# io.net
KiCad netlist of a schematic drawn in Altium Designer
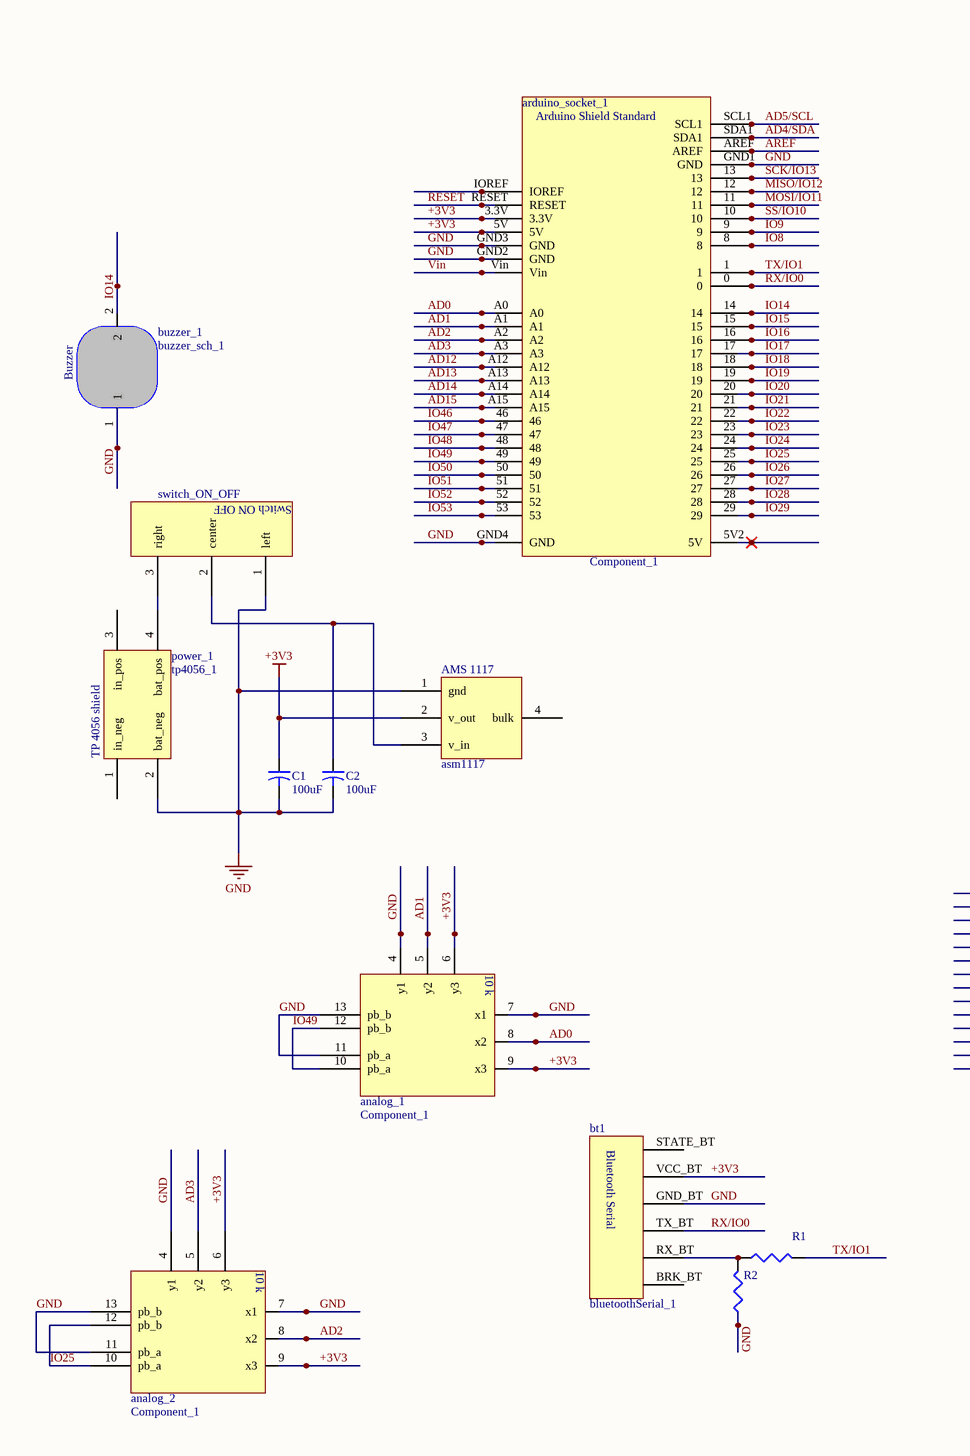
[diagram p0: io.SchDoc, left]
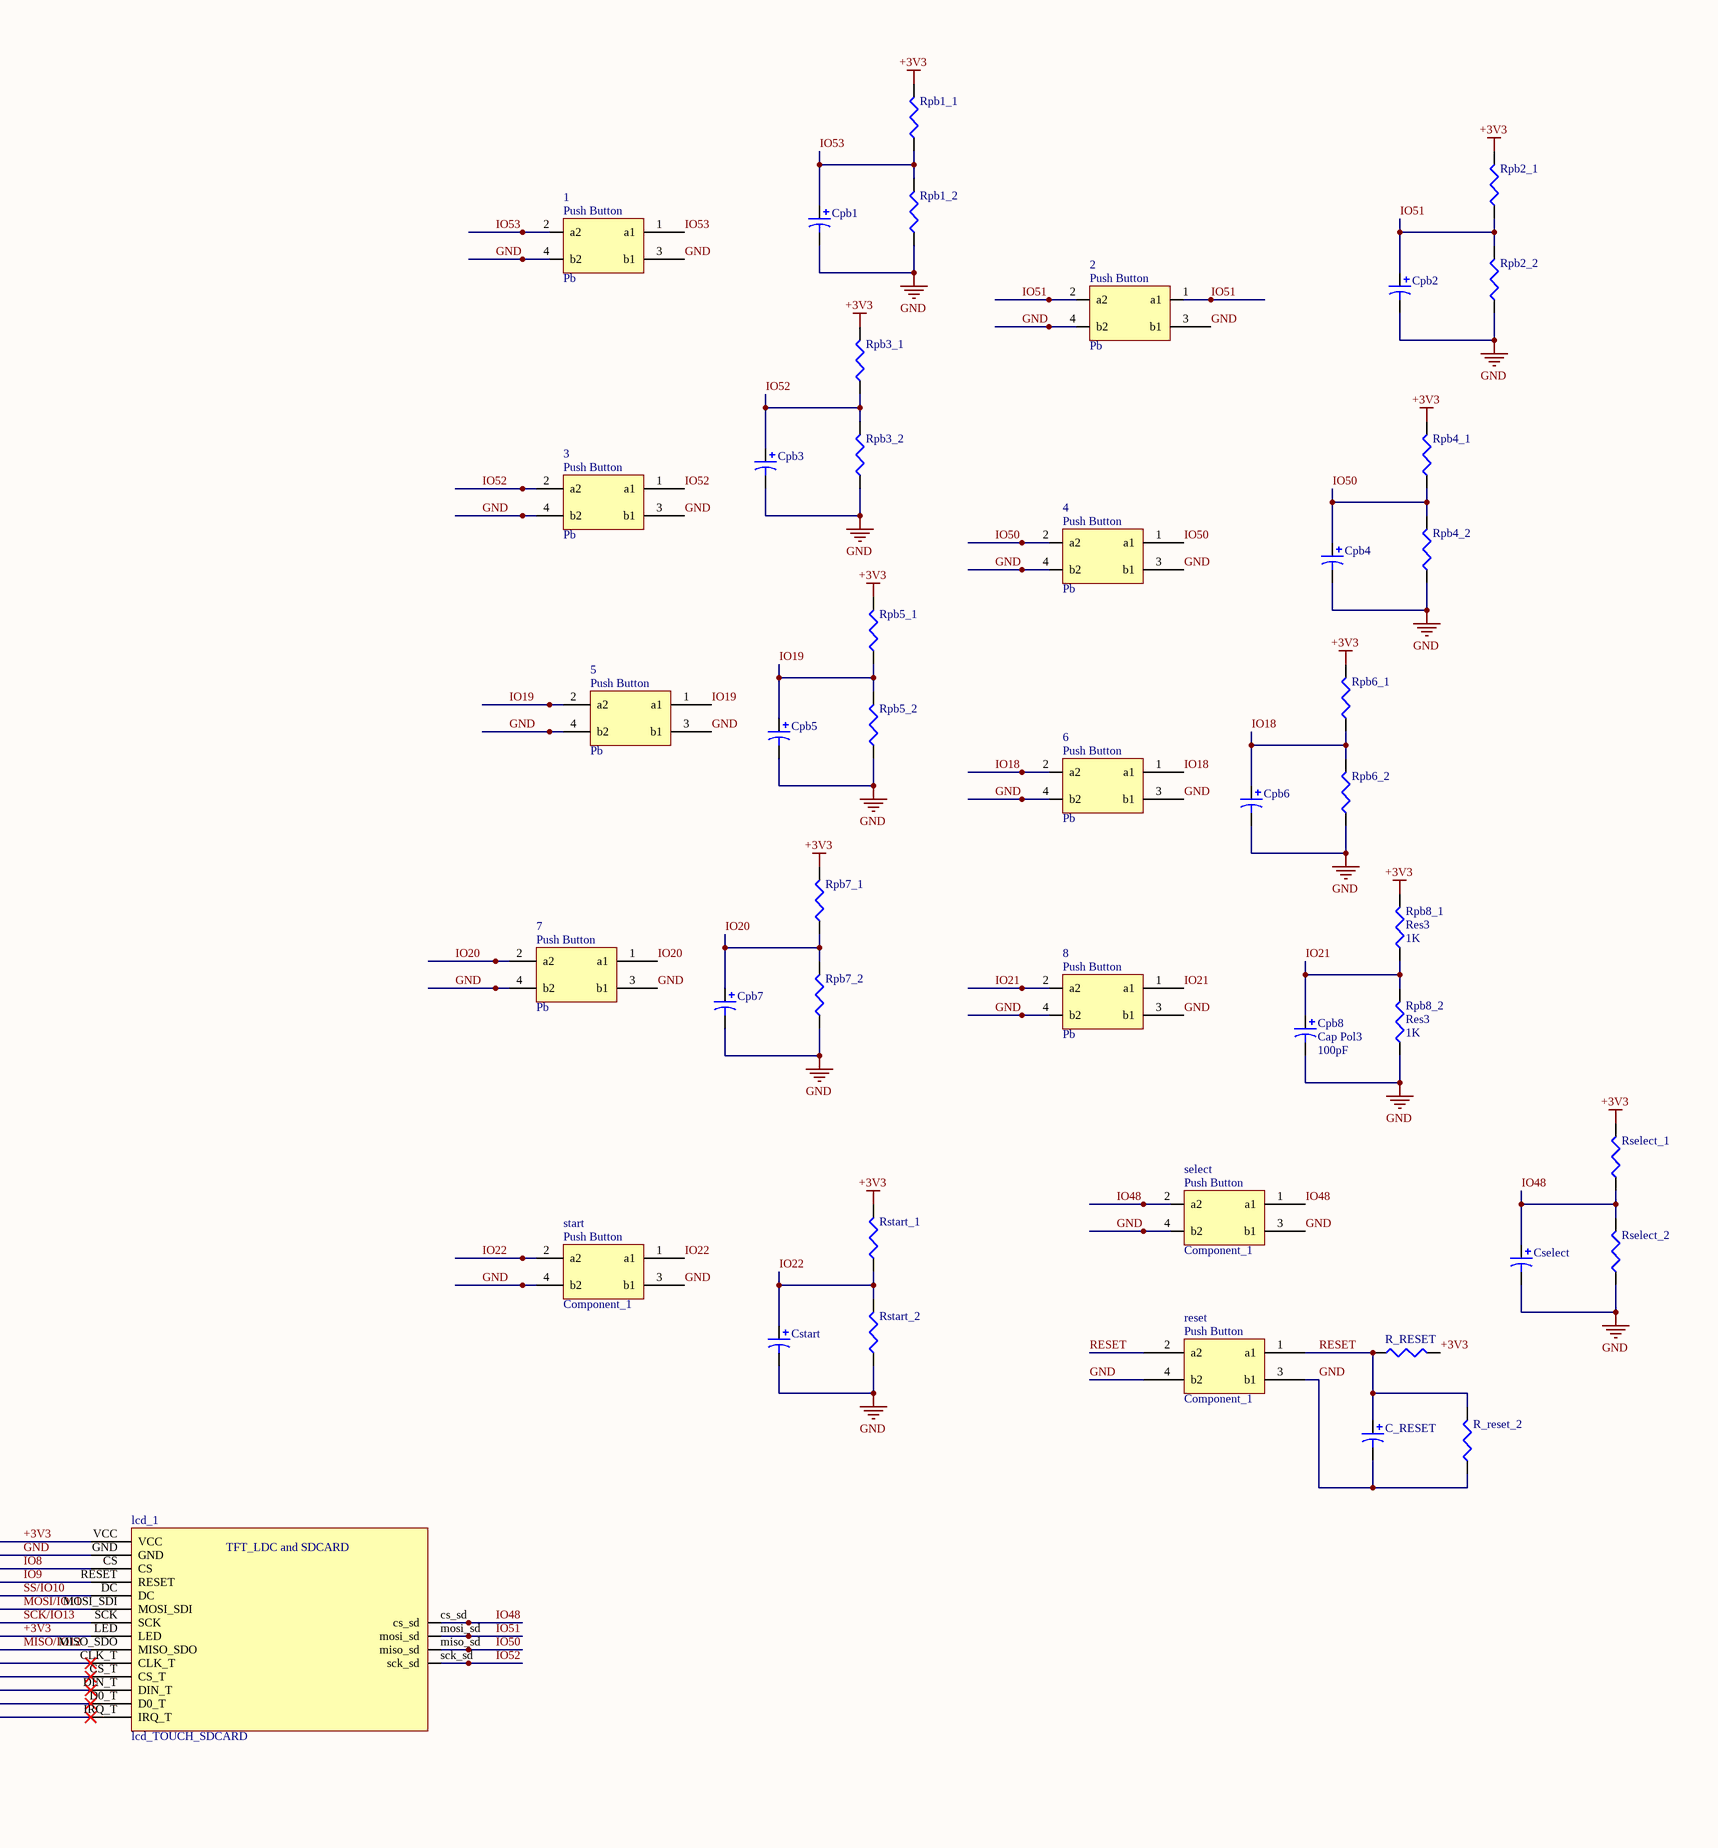
[diagram p1: io.SchDoc, right]

(export (version "E")
  (design (tool "Eeschema 10.0.6"))
  (components
    (comp (ref "1")
      (value "Pb")
      (footprint "PCBComponent_1")
      (libsource (lib "pushButton") (part "Component_1"))
    )
    (comp (ref "2")
      (value "Pb")
      (footprint "PCBComponent_1")
      (libsource (lib "pushButton") (part "Component_1"))
    )
    (comp (ref "3")
      (value "Pb")
      (footprint "PCBComponent_1")
      (libsource (lib "pushButton") (part "Component_1"))
    )
    (comp (ref "4")
      (value "Pb")
      (footprint "PCBComponent_1")
      (libsource (lib "pushButton") (part "Component_1"))
    )
    (comp (ref "5")
      (value "Pb")
      (footprint "PCBComponent_1")
      (libsource (lib "pushButton") (part "Component_1"))
    )
    (comp (ref "6")
      (value "Pb")
      (footprint "PCBComponent_1")
      (libsource (lib "pushButton") (part "Component_1"))
    )
    (comp (ref "7")
      (value "Pb")
      (footprint "PCBComponent_1")
      (libsource (lib "pushButton") (part "Component_1"))
    )
    (comp (ref "8")
      (value "Pb")
      (footprint "PCBComponent_1")
      (libsource (lib "pushButton") (part "Component_1"))
    )
    (comp (ref "analog_1")
      (value "Component_1")
      (footprint "PCBComponent_1")
      (libsource (lib "potDir_2eixos_v1_sch") (part "Component_1"))
    )
    (comp (ref "analog_2")
      (value "Component_1")
      (footprint "PCBComponent_1")
      (libsource (lib "potDir_2eixos_v1_sch") (part "Component_1"))
    )
    (comp (ref "arduino_socket_1")
      (value "Component_1")
      (footprint "arduino_due_cutPin")
      (libsource (lib "arduino_shield_stardard") (part "Component_1"))
    )
    (comp (ref "asm1117")
      (value "Component_1")
      (footprint "sot223_plasticPackage")
      (libsource (lib "AMS_1117_sch") (part "Component_1"))
    )
    (comp (ref "bt1")
      (value "bluetoothSerial_1")
      (footprint "bluetoothSerial_header")
      (libsource (lib "bluetooth_serial") (part "bluetoothSerial_1"))
    )
    (comp (ref "buzzer_1")
      (value "buzzer_sch_1")
      (footprint "buzzer_pcb_1")
      (libsource (lib "buzzer_sch") (part "buzzer_sch_1"))
    )
    (comp (ref "C1")
      (value "100uF")
      (footprint "capaEletrolitic_100uF_25v_smd")
      (description "Capacitor")
      (fields (field (name "Comment") "Cap2") (field (name "PUBLISHER") "Altium Limited"))
      (libsource (lib "Miscellaneous Devices") (part "Cap2"))
    )
    (comp (ref "C2")
      (value "100uF")
      (footprint "capaEletrolitic_100uF_25v_smd")
      (description "Capacitor")
      (fields (field (name "Comment") "Cap2") (field (name "PUBLISHER") "Altium Limited"))
      (libsource (lib "Miscellaneous Devices") (part "Cap2"))
    )
    (comp (ref "Cpb1")
      (value "Cap Pol3")
      (footprint "C0805")
      (description "Polarized Capacitor (Surface Mount)")
      (fields (field (name "PUBLISHER") "Altium Limited"))
      (libsource (lib "Miscellaneous Devices") (part "Cap Pol3"))
    )
    (comp (ref "Cpb2")
      (value "Cap Pol3")
      (footprint "C0805")
      (description "Polarized Capacitor (Surface Mount)")
      (fields (field (name "PUBLISHER") "Altium Limited"))
      (libsource (lib "Miscellaneous Devices") (part "Cap Pol3"))
    )
    (comp (ref "Cpb3")
      (value "Cap Pol3")
      (footprint "C0805")
      (description "Polarized Capacitor (Surface Mount)")
      (fields (field (name "PUBLISHER") "Altium Limited"))
      (libsource (lib "Miscellaneous Devices") (part "Cap Pol3"))
    )
    (comp (ref "Cpb4")
      (value "Cap Pol3")
      (footprint "C0805")
      (description "Polarized Capacitor (Surface Mount)")
      (fields (field (name "PUBLISHER") "Altium Limited"))
      (libsource (lib "Miscellaneous Devices") (part "Cap Pol3"))
    )
    (comp (ref "Cpb5")
      (value "Cap Pol3")
      (footprint "C0805")
      (description "Polarized Capacitor (Surface Mount)")
      (fields (field (name "PUBLISHER") "Altium Limited"))
      (libsource (lib "Miscellaneous Devices") (part "Cap Pol3"))
    )
    (comp (ref "Cpb6")
      (value "Cap Pol3")
      (footprint "C0805")
      (description "Polarized Capacitor (Surface Mount)")
      (fields (field (name "PUBLISHER") "Altium Limited"))
      (libsource (lib "Miscellaneous Devices") (part "Cap Pol3"))
    )
    (comp (ref "Cpb7")
      (value "Cap Pol3")
      (footprint "C0805")
      (description "Polarized Capacitor (Surface Mount)")
      (fields (field (name "PUBLISHER") "Altium Limited"))
      (libsource (lib "Miscellaneous Devices") (part "Cap Pol3"))
    )
    (comp (ref "Cpb8")
      (value "Cap Pol3")
      (footprint "C0805")
      (description "Polarized Capacitor (Surface Mount)")
      (fields (field (name "ALTIUM_VALUE") "100pF") (field (name "PUBLISHER") "Altium Limited"))
      (libsource (lib "Miscellaneous Devices") (part "Cap Pol3"))
    )
    (comp (ref "Cselect")
      (value "Cap Pol3")
      (footprint "C0805")
      (description "Polarized Capacitor (Surface Mount)")
      (fields (field (name "PUBLISHER") "Altium Limited"))
      (libsource (lib "Miscellaneous Devices") (part "Cap Pol3"))
    )
    (comp (ref "Cstart")
      (value "Cap Pol3")
      (footprint "C0805")
      (description "Polarized Capacitor (Surface Mount)")
      (fields (field (name "PUBLISHER") "Altium Limited"))
      (libsource (lib "Miscellaneous Devices") (part "Cap Pol3"))
    )
    (comp (ref "C_RESET")
      (value "Cap Pol3")
      (footprint "C0805")
      (description "Polarized Capacitor (Surface Mount)")
      (fields (field (name "PUBLISHER") "Altium Limited"))
      (libsource (lib "Miscellaneous Devices") (part "Cap Pol3"))
    )
    (comp (ref "lcd_1")
      (value "lcd_TOUCH_SDCARD")
      (footprint "PCB_LCDandTOUCH")
      (libsource (lib "lcd_TFT_and_TOUCH") (part "lcd_TOUCH_SDCARD"))
    )
    (comp (ref "power_1")
      (value "tp4056_1")
      (footprint "tp4056pcb_1")
      (libsource (lib "tp4056_shield_sch") (part "tp4056_1"))
    )
    (comp (ref "R1")
      (value "Res3")
      (footprint "J1-0603")
      (description "Resistor")
      (fields (field (name "PUBLISHER") "Altium Limited"))
      (libsource (lib "Miscellaneous Devices") (part "Res3"))
    )
    (comp (ref "R2")
      (value "Res3")
      (footprint "J1-0603")
      (description "Resistor")
      (fields (field (name "PUBLISHER") "Altium Limited"))
      (libsource (lib "Miscellaneous Devices") (part "Res3"))
    )
    (comp (ref "reset")
      (value "Component_1")
      (footprint "pb_6mm_1")
      (libsource (lib "pushButton") (part "Component_1"))
    )
    (comp (ref "Rpb1_1")
      (value "Res3")
      (footprint "J1-0603")
      (description "Resistor")
      (fields (field (name "PUBLISHER") "Altium Limited"))
      (libsource (lib "Miscellaneous Devices") (part "Res3"))
    )
    (comp (ref "Rpb1_2")
      (value "Res3")
      (footprint "J1-0603")
      (description "Resistor")
      (fields (field (name "PUBLISHER") "Altium Limited"))
      (libsource (lib "Miscellaneous Devices") (part "Res3"))
    )
    (comp (ref "Rpb2_1")
      (value "Res3")
      (footprint "J1-0603")
      (description "Resistor")
      (fields (field (name "PUBLISHER") "Altium Limited"))
      (libsource (lib "Miscellaneous Devices") (part "Res3"))
    )
    (comp (ref "Rpb2_2")
      (value "Res3")
      (footprint "J1-0603")
      (description "Resistor")
      (fields (field (name "PUBLISHER") "Altium Limited"))
      (libsource (lib "Miscellaneous Devices") (part "Res3"))
    )
    (comp (ref "Rpb3_1")
      (value "Res3")
      (footprint "J1-0603")
      (description "Resistor")
      (fields (field (name "PUBLISHER") "Altium Limited"))
      (libsource (lib "Miscellaneous Devices") (part "Res3"))
    )
    (comp (ref "Rpb3_2")
      (value "Res3")
      (footprint "J1-0603")
      (description "Resistor")
      (fields (field (name "PUBLISHER") "Altium Limited"))
      (libsource (lib "Miscellaneous Devices") (part "Res3"))
    )
    (comp (ref "Rpb4_1")
      (value "Res3")
      (footprint "J1-0603")
      (description "Resistor")
      (fields (field (name "PUBLISHER") "Altium Limited"))
      (libsource (lib "Miscellaneous Devices") (part "Res3"))
    )
    (comp (ref "Rpb4_2")
      (value "Res3")
      (footprint "J1-0603")
      (description "Resistor")
      (fields (field (name "PUBLISHER") "Altium Limited"))
      (libsource (lib "Miscellaneous Devices") (part "Res3"))
    )
    (comp (ref "Rpb5_1")
      (value "Res3")
      (footprint "J1-0603")
      (description "Resistor")
      (fields (field (name "PUBLISHER") "Altium Limited"))
      (libsource (lib "Miscellaneous Devices") (part "Res3"))
    )
    (comp (ref "Rpb5_2")
      (value "Res3")
      (footprint "J1-0603")
      (description "Resistor")
      (fields (field (name "PUBLISHER") "Altium Limited"))
      (libsource (lib "Miscellaneous Devices") (part "Res3"))
    )
    (comp (ref "Rpb6_1")
      (value "Res3")
      (footprint "J1-0603")
      (description "Resistor")
      (fields (field (name "PUBLISHER") "Altium Limited"))
      (libsource (lib "Miscellaneous Devices") (part "Res3"))
    )
    (comp (ref "Rpb6_2")
      (value "Res3")
      (footprint "J1-0603")
      (description "Resistor")
      (fields (field (name "PUBLISHER") "Altium Limited"))
      (libsource (lib "Miscellaneous Devices") (part "Res3"))
    )
    (comp (ref "Rpb7_1")
      (value "Res3")
      (footprint "J1-0603")
      (description "Resistor")
      (fields (field (name "PUBLISHER") "Altium Limited"))
      (libsource (lib "Miscellaneous Devices") (part "Res3"))
    )
    (comp (ref "Rpb7_2")
      (value "Res3")
      (footprint "J1-0603")
      (description "Resistor")
      (fields (field (name "PUBLISHER") "Altium Limited"))
      (libsource (lib "Miscellaneous Devices") (part "Res3"))
    )
    (comp (ref "Rpb8_1")
      (value "Res3")
      (footprint "J1-0603")
      (description "Resistor")
      (fields (field (name "ALTIUM_VALUE") "1K") (field (name "PUBLISHER") "Altium Limited"))
      (libsource (lib "Miscellaneous Devices") (part "Res3"))
    )
    (comp (ref "Rpb8_2")
      (value "Res3")
      (footprint "J1-0603")
      (description "Resistor")
      (fields (field (name "ALTIUM_VALUE") "1K") (field (name "PUBLISHER") "Altium Limited"))
      (libsource (lib "Miscellaneous Devices") (part "Res3"))
    )
    (comp (ref "Rselect_1")
      (value "Res3")
      (footprint "J1-0603")
      (description "Resistor")
      (fields (field (name "PUBLISHER") "Altium Limited"))
      (libsource (lib "Miscellaneous Devices") (part "Res3"))
    )
    (comp (ref "Rselect_2")
      (value "Res3")
      (footprint "J1-0603")
      (description "Resistor")
      (fields (field (name "PUBLISHER") "Altium Limited"))
      (libsource (lib "Miscellaneous Devices") (part "Res3"))
    )
    (comp (ref "Rstart_1")
      (value "Res3")
      (footprint "J1-0603")
      (description "Resistor")
      (fields (field (name "PUBLISHER") "Altium Limited"))
      (libsource (lib "Miscellaneous Devices") (part "Res3"))
    )
    (comp (ref "Rstart_2")
      (value "Res3")
      (footprint "J1-0603")
      (description "Resistor")
      (fields (field (name "PUBLISHER") "Altium Limited"))
      (libsource (lib "Miscellaneous Devices") (part "Res3"))
    )
    (comp (ref "R_RESET")
      (value "Res3")
      (footprint "J1-0603")
      (description "Resistor")
      (fields (field (name "PUBLISHER") "Altium Limited"))
      (libsource (lib "Miscellaneous Devices") (part "Res3"))
    )
    (comp (ref "R_reset_2")
      (value "Res3")
      (footprint "J1-0603")
      (description "Resistor")
      (fields (field (name "PUBLISHER") "Altium Limited"))
      (libsource (lib "Miscellaneous Devices") (part "Res3"))
    )
    (comp (ref "select")
      (value "Component_1")
      (footprint "PCBComponent_1")
      (libsource (lib "pushButton") (part "Component_1"))
    )
    (comp (ref "start")
      (value "Component_1")
      (footprint "PCBComponent_1")
      (libsource (lib "pushButton") (part "Component_1"))
    )
    (comp (ref "switch_ON_OFF")
      (value "switch_ON_OFF_1")
      (footprint "VERTICAL_SLIDE_SWITCH_SS12F23:PCBComponent_1")
      (libsource (lib "switch_ON_OFF") (part "switch_ON_OFF_1"))
    )
  )
  (nets
    (net (code "1") (name "+3V3") (class "Default")
      (node (ref "C1") (pin "1") (pinfunction "1_1") (pintype "passive"))
      (node (ref "R_RESET") (pin "2") (pinfunction "2_2") (pintype "passive"))
      (node (ref "Rpb1_1") (pin "2") (pinfunction "2_2") (pintype "passive"))
      (node (ref "Rpb2_1") (pin "2") (pinfunction "2_2") (pintype "passive"))
      (node (ref "Rpb3_1") (pin "2") (pinfunction "2_2") (pintype "passive"))
      (node (ref "Rpb4_1") (pin "2") (pinfunction "2_2") (pintype "passive"))
      (node (ref "Rpb5_1") (pin "2") (pinfunction "2_2") (pintype "passive"))
      (node (ref "Rpb6_1") (pin "2") (pinfunction "2_2") (pintype "passive"))
      (node (ref "Rpb7_1") (pin "2") (pinfunction "2_2") (pintype "passive"))
      (node (ref "Rpb8_1") (pin "2") (pinfunction "2_2") (pintype "passive"))
      (node (ref "Rselect_1") (pin "2") (pinfunction "2_2") (pintype "passive"))
      (node (ref "Rstart_1") (pin "2") (pinfunction "2_2") (pintype "passive"))
      (node (ref "analog_1") (pin "6") (pinfunction "y3_6") (pintype "passive"))
      (node (ref "analog_1") (pin "9") (pinfunction "x3_9") (pintype "passive"))
      (node (ref "analog_2") (pin "6") (pinfunction "y3_6") (pintype "passive"))
      (node (ref "analog_2") (pin "9") (pinfunction "x3_9") (pintype "passive"))
      (node (ref "arduino_socket_1") (pin "3.3V") (pinfunction "3.3V_3.3V") (pintype "passive"))
      (node (ref "arduino_socket_1") (pin "5V") (pinfunction "5V_5V") (pintype "passive"))
      (node (ref "asm1117") (pin "2") (pinfunction "v_out_2") (pintype "passive"))
      (node (ref "bt1") (pin "VCC_BT") (pinfunction "VCC_BT_VCC_BT") (pintype "passive"))
      (node (ref "lcd_1") (pin "LED") (pinfunction "LED_LED") (pintype "passive"))
      (node (ref "lcd_1") (pin "VCC") (pinfunction "VCC_VCC") (pintype "passive"))
    )
    (net (code "2") (name "/AD0") (class "Default")
      (node (ref "analog_1") (pin "8") (pinfunction "x2_8") (pintype "passive"))
      (node (ref "arduino_socket_1") (pin "A0") (pinfunction "A0_A0") (pintype "passive"))
    )
    (net (code "3") (name "/AD1") (class "Default")
      (node (ref "analog_1") (pin "5") (pinfunction "y2_5") (pintype "passive"))
      (node (ref "arduino_socket_1") (pin "A1") (pinfunction "A1_A1") (pintype "passive"))
    )
    (net (code "4") (name "/AD2") (class "Default")
      (node (ref "analog_2") (pin "8") (pinfunction "x2_8") (pintype "passive"))
      (node (ref "arduino_socket_1") (pin "A2") (pinfunction "A2_A2") (pintype "passive"))
    )
    (net (code "5") (name "/AD3") (class "Default")
      (node (ref "analog_2") (pin "5") (pinfunction "y2_5") (pintype "passive"))
      (node (ref "arduino_socket_1") (pin "A3") (pinfunction "A3_A3") (pintype "passive"))
    )
    (net (code "6") (name "/AD4{slash}SDA") (class "Default")
      (node (ref "arduino_socket_1") (pin "SDA1") (pinfunction "SDA1_SDA1") (pintype "passive"))
    )
    (net (code "7") (name "/AD5{slash}SCL") (class "Default")
      (node (ref "arduino_socket_1") (pin "SCL1") (pinfunction "SCL1_SCL1") (pintype "passive"))
    )
    (net (code "8") (name "/AD12") (class "Default")
      (node (ref "arduino_socket_1") (pin "A12") (pinfunction "A12_A12") (pintype "passive"))
    )
    (net (code "9") (name "/AD13") (class "Default")
      (node (ref "arduino_socket_1") (pin "A13") (pinfunction "A13_A13") (pintype "passive"))
    )
    (net (code "10") (name "/AD14") (class "Default")
      (node (ref "arduino_socket_1") (pin "A14") (pinfunction "A14_A14") (pintype "passive"))
    )
    (net (code "11") (name "/AD15") (class "Default")
      (node (ref "arduino_socket_1") (pin "A15") (pinfunction "A15_A15") (pintype "passive"))
    )
    (net (code "12") (name "/AREF") (class "Default")
      (node (ref "arduino_socket_1") (pin "AREF") (pinfunction "AREF_AREF") (pintype "passive"))
    )
    (net (code "13") (name "/IO8") (class "Default")
      (node (ref "arduino_socket_1") (pin "8") (pinfunction "8_8") (pintype "passive"))
      (node (ref "lcd_1") (pin "CS") (pinfunction "CS_CS") (pintype "passive"))
    )
    (net (code "14") (name "/IO9") (class "Default")
      (node (ref "arduino_socket_1") (pin "9") (pinfunction "9_9") (pintype "passive"))
      (node (ref "lcd_1") (pin "RESET") (pinfunction "RESET_RESET") (pintype "passive"))
    )
    (net (code "15") (name "/IO14") (class "Default")
      (node (ref "arduino_socket_1") (pin "14") (pinfunction "14_14") (pintype "passive"))
      (node (ref "buzzer_1") (pin "2") (pinfunction "2_2") (pintype "passive"))
    )
    (net (code "16") (name "/IO15") (class "Default")
      (node (ref "arduino_socket_1") (pin "15") (pinfunction "15_15") (pintype "passive"))
    )
    (net (code "17") (name "/IO16") (class "Default")
      (node (ref "arduino_socket_1") (pin "16") (pinfunction "16_16") (pintype "passive"))
    )
    (net (code "18") (name "/IO17") (class "Default")
      (node (ref "arduino_socket_1") (pin "17") (pinfunction "17_17") (pintype "passive"))
    )
    (net (code "19") (name "/IO18") (class "Default")
      (node (ref "6") (pin "1") (pinfunction "a1_1") (pintype "passive"))
      (node (ref "6") (pin "2") (pinfunction "a2_2") (pintype "passive"))
      (node (ref "Cpb6") (pin "1") (pinfunction "1_1") (pintype "passive"))
      (node (ref "Rpb6_1") (pin "1") (pinfunction "1_1") (pintype "passive"))
      (node (ref "Rpb6_2") (pin "2") (pinfunction "2_2") (pintype "passive"))
      (node (ref "arduino_socket_1") (pin "18") (pinfunction "18_18") (pintype "passive"))
    )
    (net (code "20") (name "/IO19") (class "Default")
      (node (ref "5") (pin "1") (pinfunction "a1_1") (pintype "passive"))
      (node (ref "5") (pin "2") (pinfunction "a2_2") (pintype "passive"))
      (node (ref "Cpb5") (pin "1") (pinfunction "1_1") (pintype "passive"))
      (node (ref "Rpb5_1") (pin "1") (pinfunction "1_1") (pintype "passive"))
      (node (ref "Rpb5_2") (pin "2") (pinfunction "2_2") (pintype "passive"))
      (node (ref "arduino_socket_1") (pin "19") (pinfunction "19_19") (pintype "passive"))
    )
    (net (code "21") (name "/IO20") (class "Default")
      (node (ref "7") (pin "1") (pinfunction "a1_1") (pintype "passive"))
      (node (ref "7") (pin "2") (pinfunction "a2_2") (pintype "passive"))
      (node (ref "Cpb7") (pin "1") (pinfunction "1_1") (pintype "passive"))
      (node (ref "Rpb7_1") (pin "1") (pinfunction "1_1") (pintype "passive"))
      (node (ref "Rpb7_2") (pin "2") (pinfunction "2_2") (pintype "passive"))
      (node (ref "arduino_socket_1") (pin "20") (pinfunction "20_20") (pintype "passive"))
    )
    (net (code "22") (name "/IO21") (class "Default")
      (node (ref "8") (pin "1") (pinfunction "a1_1") (pintype "passive"))
      (node (ref "8") (pin "2") (pinfunction "a2_2") (pintype "passive"))
      (node (ref "Cpb8") (pin "1") (pinfunction "1_1") (pintype "passive"))
      (node (ref "Rpb8_1") (pin "1") (pinfunction "1_1") (pintype "passive"))
      (node (ref "Rpb8_2") (pin "2") (pinfunction "2_2") (pintype "passive"))
      (node (ref "arduino_socket_1") (pin "21") (pinfunction "21_21") (pintype "passive"))
    )
    (net (code "23") (name "/IO22") (class "Default")
      (node (ref "Cstart") (pin "1") (pinfunction "1_1") (pintype "passive"))
      (node (ref "Rstart_1") (pin "1") (pinfunction "1_1") (pintype "passive"))
      (node (ref "Rstart_2") (pin "2") (pinfunction "2_2") (pintype "passive"))
      (node (ref "arduino_socket_1") (pin "22") (pinfunction "22_22") (pintype "passive"))
      (node (ref "start") (pin "1") (pinfunction "a1_1") (pintype "passive"))
      (node (ref "start") (pin "2") (pinfunction "a2_2") (pintype "passive"))
    )
    (net (code "24") (name "/IO23") (class "Default")
      (node (ref "arduino_socket_1") (pin "23") (pinfunction "23_23") (pintype "passive"))
    )
    (net (code "25") (name "/IO24") (class "Default")
      (node (ref "arduino_socket_1") (pin "24") (pinfunction "24_24") (pintype "passive"))
    )
    (net (code "26") (name "/IO25") (class "Default")
      (node (ref "analog_2") (pin "10") (pinfunction "pb_a_10") (pintype "passive"))
      (node (ref "analog_2") (pin "12") (pinfunction "pb_b_12") (pintype "passive"))
      (node (ref "arduino_socket_1") (pin "25") (pinfunction "25_25") (pintype "passive"))
    )
    (net (code "27") (name "/IO26") (class "Default")
      (node (ref "arduino_socket_1") (pin "26") (pinfunction "26_26") (pintype "passive"))
    )
    (net (code "28") (name "/IO27") (class "Default")
      (node (ref "arduino_socket_1") (pin "27") (pinfunction "27_27") (pintype "passive"))
    )
    (net (code "29") (name "/IO28") (class "Default")
      (node (ref "arduino_socket_1") (pin "28") (pinfunction "28_28") (pintype "passive"))
    )
    (net (code "30") (name "/IO29") (class "Default")
      (node (ref "arduino_socket_1") (pin "29") (pinfunction "29_29") (pintype "passive"))
    )
    (net (code "31") (name "/IO46") (class "Default")
      (node (ref "arduino_socket_1") (pin "46") (pinfunction "46_46") (pintype "passive"))
    )
    (net (code "32") (name "/IO47") (class "Default")
      (node (ref "arduino_socket_1") (pin "47") (pinfunction "47_47") (pintype "passive"))
    )
    (net (code "33") (name "/IO48") (class "Default")
      (node (ref "Cselect") (pin "1") (pinfunction "1_1") (pintype "passive"))
      (node (ref "Rselect_1") (pin "1") (pinfunction "1_1") (pintype "passive"))
      (node (ref "Rselect_2") (pin "2") (pinfunction "2_2") (pintype "passive"))
      (node (ref "arduino_socket_1") (pin "48") (pinfunction "48_48") (pintype "passive"))
      (node (ref "lcd_1") (pin "cs_sd") (pinfunction "cs_sd_cs_sd") (pintype "passive"))
      (node (ref "select") (pin "1") (pinfunction "a1_1") (pintype "passive"))
      (node (ref "select") (pin "2") (pinfunction "a2_2") (pintype "passive"))
    )
    (net (code "34") (name "/IO49") (class "Default")
      (node (ref "analog_1") (pin "10") (pinfunction "pb_a_10") (pintype "passive"))
      (node (ref "analog_1") (pin "12") (pinfunction "pb_b_12") (pintype "passive"))
      (node (ref "arduino_socket_1") (pin "49") (pinfunction "49_49") (pintype "passive"))
    )
    (net (code "35") (name "/IO50") (class "Default")
      (node (ref "4") (pin "1") (pinfunction "a1_1") (pintype "passive"))
      (node (ref "4") (pin "2") (pinfunction "a2_2") (pintype "passive"))
      (node (ref "Cpb4") (pin "1") (pinfunction "1_1") (pintype "passive"))
      (node (ref "Rpb4_1") (pin "1") (pinfunction "1_1") (pintype "passive"))
      (node (ref "Rpb4_2") (pin "2") (pinfunction "2_2") (pintype "passive"))
      (node (ref "arduino_socket_1") (pin "50") (pinfunction "50_50") (pintype "passive"))
      (node (ref "lcd_1") (pin "miso_sd") (pinfunction "miso_sd_miso_sd") (pintype "passive"))
    )
    (net (code "36") (name "/IO51") (class "Default")
      (node (ref "2") (pin "1") (pinfunction "a1_1") (pintype "passive"))
      (node (ref "2") (pin "2") (pinfunction "a2_2") (pintype "passive"))
      (node (ref "Cpb2") (pin "1") (pinfunction "1_1") (pintype "passive"))
      (node (ref "Rpb2_1") (pin "1") (pinfunction "1_1") (pintype "passive"))
      (node (ref "Rpb2_2") (pin "2") (pinfunction "2_2") (pintype "passive"))
      (node (ref "arduino_socket_1") (pin "51") (pinfunction "51_51") (pintype "passive"))
      (node (ref "lcd_1") (pin "mosi_sd") (pinfunction "mosi_sd_mosi_sd") (pintype "passive"))
    )
    (net (code "37") (name "/IO52") (class "Default")
      (node (ref "3") (pin "1") (pinfunction "a1_1") (pintype "passive"))
      (node (ref "3") (pin "2") (pinfunction "a2_2") (pintype "passive"))
      (node (ref "Cpb3") (pin "1") (pinfunction "1_1") (pintype "passive"))
      (node (ref "Rpb3_1") (pin "1") (pinfunction "1_1") (pintype "passive"))
      (node (ref "Rpb3_2") (pin "2") (pinfunction "2_2") (pintype "passive"))
      (node (ref "arduino_socket_1") (pin "52") (pinfunction "52_52") (pintype "passive"))
      (node (ref "lcd_1") (pin "sck_sd") (pinfunction "sck_sd_sck_sd") (pintype "passive"))
    )
    (net (code "38") (name "/IO53") (class "Default")
      (node (ref "1") (pin "1") (pinfunction "a1_1") (pintype "passive"))
      (node (ref "1") (pin "2") (pinfunction "a2_2") (pintype "passive"))
      (node (ref "Cpb1") (pin "1") (pinfunction "1_1") (pintype "passive"))
      (node (ref "Rpb1_1") (pin "1") (pinfunction "1_1") (pintype "passive"))
      (node (ref "Rpb1_2") (pin "2") (pinfunction "2_2") (pintype "passive"))
      (node (ref "arduino_socket_1") (pin "53") (pinfunction "53_53") (pintype "passive"))
    )
    (net (code "39") (name "/MISO{slash}IO12") (class "Default")
      (node (ref "arduino_socket_1") (pin "12") (pinfunction "12_12") (pintype "passive"))
      (node (ref "lcd_1") (pin "MISO_SDO") (pinfunction "MISO_SDO_MISO_SDO") (pintype "passive"))
    )
    (net (code "40") (name "/MOSI{slash}IO11") (class "Default")
      (node (ref "arduino_socket_1") (pin "11") (pinfunction "11_11") (pintype "passive"))
      (node (ref "lcd_1") (pin "MOSI_SDI") (pinfunction "MOSI_SDI_MOSI_SDI") (pintype "passive"))
    )
    (net (code "41") (name "/RESET") (class "Default")
      (node (ref "C_RESET") (pin "1") (pinfunction "1_1") (pintype "passive"))
      (node (ref "R_RESET") (pin "1") (pinfunction "1_1") (pintype "passive"))
      (node (ref "R_reset_2") (pin "2") (pinfunction "2_2") (pintype "passive"))
      (node (ref "arduino_socket_1") (pin "RESET") (pinfunction "RESET_RESET") (pintype "passive"))
      (node (ref "reset") (pin "1") (pinfunction "a1_1") (pintype "passive"))
      (node (ref "reset") (pin "2") (pinfunction "a2_2") (pintype "passive"))
    )
    (net (code "42") (name "/RX{slash}IO0") (class "Default")
      (node (ref "arduino_socket_1") (pin "0") (pinfunction "0_0") (pintype "passive"))
      (node (ref "bt1") (pin "TX_BT") (pinfunction "TX_BT_TX_BT") (pintype "passive"))
    )
    (net (code "43") (name "/SCK{slash}IO13") (class "Default")
      (node (ref "arduino_socket_1") (pin "13") (pinfunction "13_13") (pintype "passive"))
      (node (ref "lcd_1") (pin "SCK") (pinfunction "SCK_SCK") (pintype "passive"))
    )
    (net (code "44") (name "/SS{slash}IO10") (class "Default")
      (node (ref "arduino_socket_1") (pin "10") (pinfunction "10_10") (pintype "passive"))
      (node (ref "lcd_1") (pin "DC") (pinfunction "DC_DC") (pintype "passive"))
    )
    (net (code "45") (name "/TX{slash}IO1") (class "Default")
      (node (ref "R1") (pin "2") (pinfunction "2_2") (pintype "passive"))
      (node (ref "arduino_socket_1") (pin "1") (pinfunction "1_1") (pintype "passive"))
    )
    (net (code "46") (name "/Vin") (class "Default")
      (node (ref "arduino_socket_1") (pin "Vin") (pinfunction "Vin_Vin") (pintype "passive"))
    )
    (net (code "47") (name "GND") (class "Default")
      (node (ref "1") (pin "3") (pinfunction "b1_3") (pintype "passive"))
      (node (ref "1") (pin "4") (pinfunction "b2_4") (pintype "passive"))
      (node (ref "2") (pin "3") (pinfunction "b1_3") (pintype "passive"))
      (node (ref "2") (pin "4") (pinfunction "b2_4") (pintype "passive"))
      (node (ref "3") (pin "3") (pinfunction "b1_3") (pintype "passive"))
      (node (ref "3") (pin "4") (pinfunction "b2_4") (pintype "passive"))
      (node (ref "4") (pin "3") (pinfunction "b1_3") (pintype "passive"))
      (node (ref "4") (pin "4") (pinfunction "b2_4") (pintype "passive"))
      (node (ref "5") (pin "3") (pinfunction "b1_3") (pintype "passive"))
      (node (ref "5") (pin "4") (pinfunction "b2_4") (pintype "passive"))
      (node (ref "6") (pin "3") (pinfunction "b1_3") (pintype "passive"))
      (node (ref "6") (pin "4") (pinfunction "b2_4") (pintype "passive"))
      (node (ref "7") (pin "3") (pinfunction "b1_3") (pintype "passive"))
      (node (ref "7") (pin "4") (pinfunction "b2_4") (pintype "passive"))
      (node (ref "8") (pin "3") (pinfunction "b1_3") (pintype "passive"))
      (node (ref "8") (pin "4") (pinfunction "b2_4") (pintype "passive"))
      (node (ref "C1") (pin "2") (pinfunction "2_2") (pintype "passive"))
      (node (ref "C2") (pin "2") (pinfunction "2_2") (pintype "passive"))
      (node (ref "C_RESET") (pin "2") (pinfunction "2_2") (pintype "passive"))
      (node (ref "Cpb1") (pin "2") (pinfunction "2_2") (pintype "passive"))
      (node (ref "Cpb2") (pin "2") (pinfunction "2_2") (pintype "passive"))
      (node (ref "Cpb3") (pin "2") (pinfunction "2_2") (pintype "passive"))
      (node (ref "Cpb4") (pin "2") (pinfunction "2_2") (pintype "passive"))
      (node (ref "Cpb5") (pin "2") (pinfunction "2_2") (pintype "passive"))
      (node (ref "Cpb6") (pin "2") (pinfunction "2_2") (pintype "passive"))
      (node (ref "Cpb7") (pin "2") (pinfunction "2_2") (pintype "passive"))
      (node (ref "Cpb8") (pin "2") (pinfunction "2_2") (pintype "passive"))
      (node (ref "Cselect") (pin "2") (pinfunction "2_2") (pintype "passive"))
      (node (ref "Cstart") (pin "2") (pinfunction "2_2") (pintype "passive"))
      (node (ref "R2") (pin "1") (pinfunction "1_1") (pintype "passive"))
      (node (ref "R_reset_2") (pin "1") (pinfunction "1_1") (pintype "passive"))
      (node (ref "Rpb1_2") (pin "1") (pinfunction "1_1") (pintype "passive"))
      (node (ref "Rpb2_2") (pin "1") (pinfunction "1_1") (pintype "passive"))
      (node (ref "Rpb3_2") (pin "1") (pinfunction "1_1") (pintype "passive"))
      (node (ref "Rpb4_2") (pin "1") (pinfunction "1_1") (pintype "passive"))
      (node (ref "Rpb5_2") (pin "1") (pinfunction "1_1") (pintype "passive"))
      (node (ref "Rpb6_2") (pin "1") (pinfunction "1_1") (pintype "passive"))
      (node (ref "Rpb7_2") (pin "1") (pinfunction "1_1") (pintype "passive"))
      (node (ref "Rpb8_2") (pin "1") (pinfunction "1_1") (pintype "passive"))
      (node (ref "Rselect_2") (pin "1") (pinfunction "1_1") (pintype "passive"))
      (node (ref "Rstart_2") (pin "1") (pinfunction "1_1") (pintype "passive"))
      (node (ref "analog_1") (pin "11") (pinfunction "pb_a_11") (pintype "passive"))
      (node (ref "analog_1") (pin "13") (pinfunction "pb_b_13") (pintype "passive"))
      (node (ref "analog_1") (pin "4") (pinfunction "y1_4") (pintype "passive"))
      (node (ref "analog_1") (pin "7") (pinfunction "x1_7") (pintype "passive"))
      (node (ref "analog_2") (pin "11") (pinfunction "pb_a_11") (pintype "passive"))
      (node (ref "analog_2") (pin "13") (pinfunction "pb_b_13") (pintype "passive"))
      (node (ref "analog_2") (pin "4") (pinfunction "y1_4") (pintype "passive"))
      (node (ref "analog_2") (pin "7") (pinfunction "x1_7") (pintype "passive"))
      (node (ref "arduino_socket_1") (pin "GND1") (pinfunction "GND_GND1") (pintype "passive"))
      (node (ref "arduino_socket_1") (pin "GND2") (pinfunction "GND_GND2") (pintype "passive"))
      (node (ref "arduino_socket_1") (pin "GND3") (pinfunction "GND_GND3") (pintype "passive"))
      (node (ref "arduino_socket_1") (pin "GND4") (pinfunction "GND_GND4") (pintype "passive"))
      (node (ref "asm1117") (pin "1") (pinfunction "gnd_1") (pintype "passive"))
      (node (ref "bt1") (pin "GND_BT") (pinfunction "GND_BT_GND_BT") (pintype "passive"))
      (node (ref "buzzer_1") (pin "1") (pinfunction "1_1") (pintype "passive"))
      (node (ref "lcd_1") (pin "GND") (pinfunction "GND_GND") (pintype "passive"))
      (node (ref "power_1") (pin "2") (pinfunction "bat_neg_2") (pintype "passive"))
      (node (ref "reset") (pin "3") (pinfunction "b1_3") (pintype "passive"))
      (node (ref "reset") (pin "4") (pinfunction "b2_4") (pintype "passive"))
      (node (ref "select") (pin "3") (pinfunction "b1_3") (pintype "passive"))
      (node (ref "select") (pin "4") (pinfunction "b2_4") (pintype "passive"))
      (node (ref "start") (pin "3") (pinfunction "b1_3") (pintype "passive"))
      (node (ref "start") (pin "4") (pinfunction "b2_4") (pintype "passive"))
      (node (ref "switch_ON_OFF") (pin "1") (pinfunction "left_1") (pintype "passive"))
    )
    (net (code "48") (name "Net-(R1-Pad1)") (class "Default")
      (node (ref "R1") (pin "1") (pinfunction "1_1") (pintype "passive"))
      (node (ref "R2") (pin "2") (pinfunction "2_2") (pintype "passive"))
      (node (ref "bt1") (pin "RX_BT") (pinfunction "RX_BT_RX_BT") (pintype "passive"))
    )
    (net (code "49") (name "Net-(asm1117-v_in)") (class "Default")
      (node (ref "C2") (pin "1") (pinfunction "1_1") (pintype "passive"))
      (node (ref "asm1117") (pin "3") (pinfunction "v_in_3") (pintype "passive"))
      (node (ref "switch_ON_OFF") (pin "2") (pinfunction "center_2") (pintype "passive"))
    )
    (net (code "50") (name "Net-(power_1-bat_pos)") (class "Default")
      (node (ref "power_1") (pin "4") (pinfunction "bat_pos_4") (pintype "passive"))
      (node (ref "switch_ON_OFF") (pin "3") (pinfunction "right_3") (pintype "passive"))
    )
    (net (code "51") (name "unconnected-(arduino_socket_1-5V-Pad5V2)") (class "Default")
      (node (ref "arduino_socket_1") (pin "5V2") (pinfunction "5V_5V2") (pintype "passive+no_connect"))
    )
    (net (code "52") (name "unconnected-(arduino_socket_1-PadIOREF)") (class "Default")
      (node (ref "arduino_socket_1") (pin "IOREF") (pinfunction "IOREF_IOREF") (pintype "passive"))
    )
    (net (code "53") (name "unconnected-(asm1117-bulk-Pad4)") (class "Default")
      (node (ref "asm1117") (pin "4") (pinfunction "bulk_4") (pintype "passive"))
    )
    (net (code "54") (name "unconnected-(bt1-PadBRK_BT)") (class "Default")
      (node (ref "bt1") (pin "BRK_BT") (pinfunction "BRK_BT_BRK_BT") (pintype "passive"))
    )
    (net (code "55") (name "unconnected-(bt1-PadSTATE_BT)") (class "Default")
      (node (ref "bt1") (pin "STATE_BT") (pinfunction "STATE_BT_STATE_BT") (pintype "passive"))
    )
    (net (code "56") (name "unconnected-(lcd_1-PadCLK_T)") (class "Default")
      (node (ref "lcd_1") (pin "CLK_T") (pinfunction "CLK_T_CLK_T") (pintype "passive+no_connect"))
    )
    (net (code "57") (name "unconnected-(lcd_1-PadCS_T)") (class "Default")
      (node (ref "lcd_1") (pin "CS_T") (pinfunction "CS_T_CS_T") (pintype "passive+no_connect"))
    )
    (net (code "58") (name "unconnected-(lcd_1-PadD0_T)") (class "Default")
      (node (ref "lcd_1") (pin "D0_T") (pinfunction "D0_T_D0_T") (pintype "passive+no_connect"))
    )
    (net (code "59") (name "unconnected-(lcd_1-PadDIN_T)") (class "Default")
      (node (ref "lcd_1") (pin "DIN_T") (pinfunction "DIN_T_DIN_T") (pintype "passive+no_connect"))
    )
    (net (code "60") (name "unconnected-(lcd_1-PadIRQ_T)") (class "Default")
      (node (ref "lcd_1") (pin "IRQ_T") (pinfunction "IRQ_T_IRQ_T") (pintype "passive+no_connect"))
    )
    (net (code "61") (name "unconnected-(power_1-in_neg-Pad1)") (class "Default")
      (node (ref "power_1") (pin "1") (pinfunction "in_neg_1") (pintype "passive"))
    )
    (net (code "62") (name "unconnected-(power_1-in_pos-Pad3)") (class "Default")
      (node (ref "power_1") (pin "3") (pinfunction "in_pos_3") (pintype "passive"))
    )
  )
)
